# ESP32-HWE-Dev-Power.net
KiCad netlist of a schematic drawn in Altium Designer
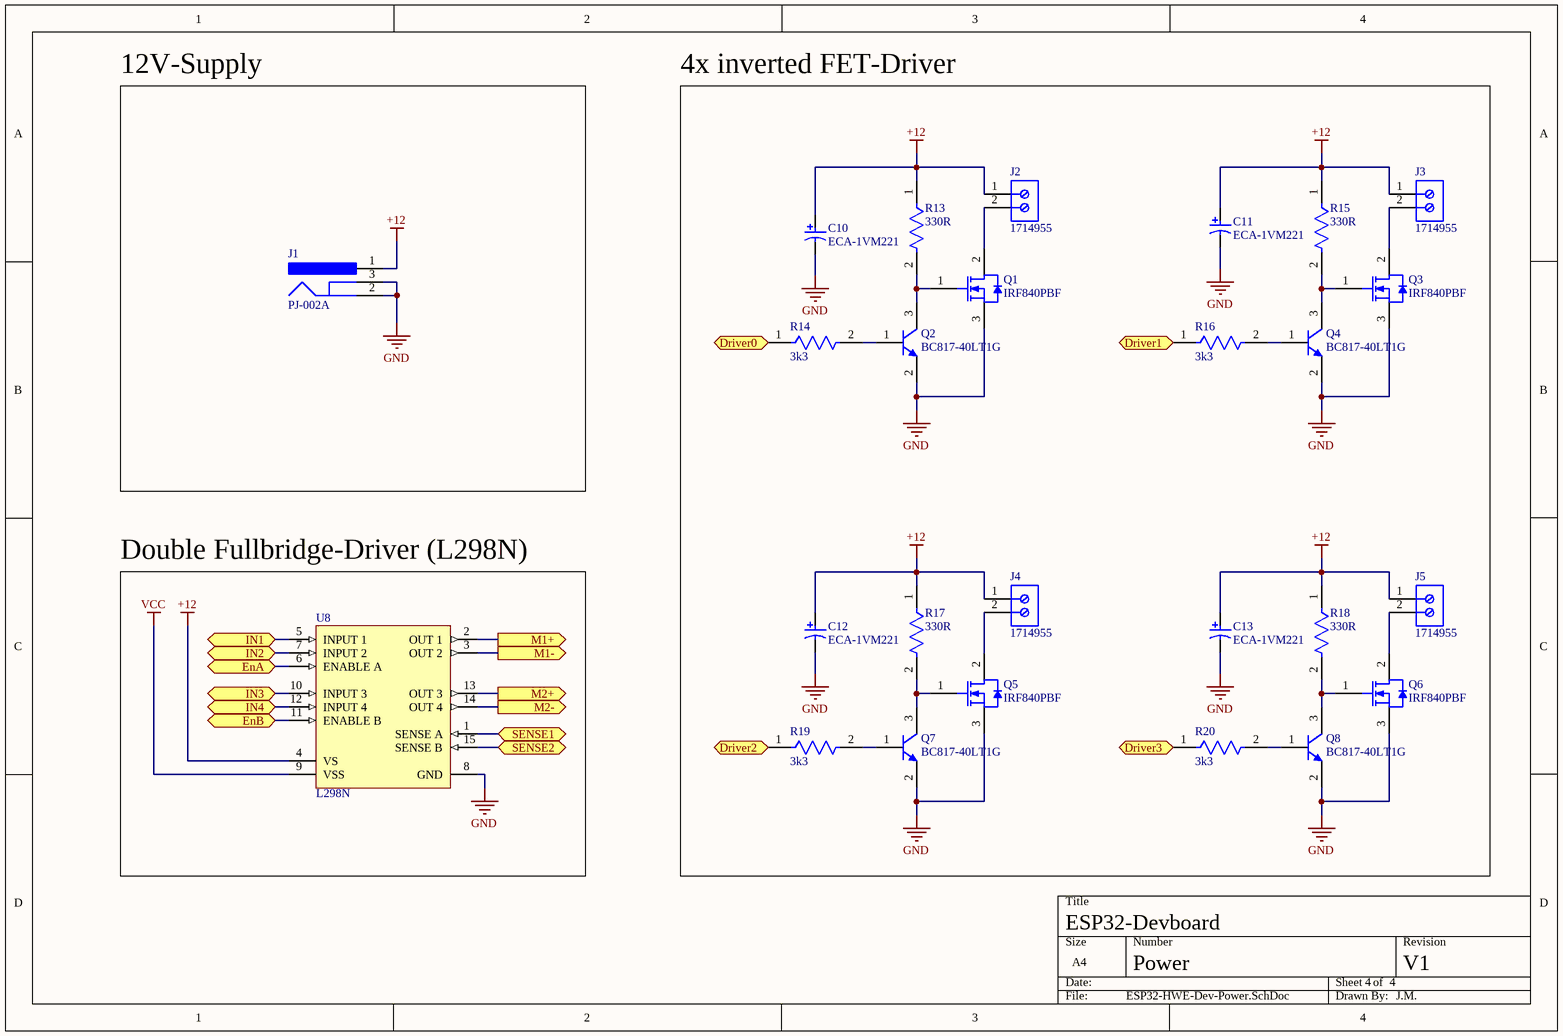
[diagram p0: ESP32-HWE-Dev-Power.SchDoc]

(export (version "E")
  (design (tool "Eeschema 10.0.6"))
  (components
    (comp (ref "C10")
      (value "ECA-1VM221")
      (footprint "PNSC-ECA-1VM221-2")
      (description "Aluminum Electrolytic Capacitor, 220 uF, +/- 20%, 35 V, -40 to 85 degC, 2-Pin THD, RoHS, Bulk")
      (fields (field (name "MANUFACTURER") "Panasonic"))
      (libsource (lib "Altium Content Vault") (part "CAP-P-2"))
    )
    (comp (ref "C11")
      (value "ECA-1VM221")
      (footprint "PNSC-ECA-1VM221-2")
      (description "Aluminum Electrolytic Capacitor, 220 uF, +/- 20%, 35 V, -40 to 85 degC, 2-Pin THD, RoHS, Bulk")
      (fields (field (name "MANUFACTURER") "Panasonic"))
      (libsource (lib "Altium Content Vault") (part "CAP-P-2"))
    )
    (comp (ref "C12")
      (value "ECA-1VM221")
      (footprint "PNSC-ECA-1VM221-2")
      (description "Aluminum Electrolytic Capacitor, 220 uF, +/- 20%, 35 V, -40 to 85 degC, 2-Pin THD, RoHS, Bulk")
      (fields (field (name "MANUFACTURER") "Panasonic"))
      (libsource (lib "Altium Content Vault") (part "CAP-P-2"))
    )
    (comp (ref "C13")
      (value "ECA-1VM221")
      (footprint "PNSC-ECA-1VM221-2")
      (description "Aluminum Electrolytic Capacitor, 220 uF, +/- 20%, 35 V, -40 to 85 degC, 2-Pin THD, RoHS, Bulk")
      (fields (field (name "MANUFACTURER") "Panasonic"))
      (libsource (lib "Altium Content Vault") (part "CAP-P-2"))
    )
    (comp (ref "J1")
      (value "PJ-002A")
      (footprint "CUI-PJ-002A_V")
      (fields (field (name "MANUFACTURER") "CUIInc."))
      (libsource (lib "Altium Content Vault") (part "JACK-2CD3-RN_B"))
    )
    (comp (ref "J2")
      (value "1714955")
      (footprint "PHOE-1714955_V")
      (description "PC Terminal Block, Pitch 6.35 mm, 1 x 2 Position, Height 21.5 mm, Tail Lenght 5.1 mm, RoHS, Bulk")
      (fields (field (name "MANUFACTURER") "Phoenix Contact"))
      (libsource (lib "Altium Content Vault") (part "CN-1P-F-TB2"))
    )
    (comp (ref "J3")
      (value "1714955")
      (footprint "PHOE-1714955_V")
      (description "PC Terminal Block, Pitch 6.35 mm, 1 x 2 Position, Height 21.5 mm, Tail Lenght 5.1 mm, RoHS, Bulk")
      (fields (field (name "MANUFACTURER") "Phoenix Contact"))
      (libsource (lib "Altium Content Vault") (part "CN-1P-F-TB2"))
    )
    (comp (ref "J4")
      (value "1714955")
      (footprint "PHOE-1714955_V")
      (description "PC Terminal Block, Pitch 6.35 mm, 1 x 2 Position, Height 21.5 mm, Tail Lenght 5.1 mm, RoHS, Bulk")
      (fields (field (name "MANUFACTURER") "Phoenix Contact"))
      (libsource (lib "Altium Content Vault") (part "CN-1P-F-TB2"))
    )
    (comp (ref "J5")
      (value "1714955")
      (footprint "PHOE-1714955_V")
      (description "PC Terminal Block, Pitch 6.35 mm, 1 x 2 Position, Height 21.5 mm, Tail Lenght 5.1 mm, RoHS, Bulk")
      (fields (field (name "MANUFACTURER") "Phoenix Contact"))
      (libsource (lib "Altium Content Vault") (part "CN-1P-F-TB2"))
    )
    (comp (ref "Q1")
      (value "IRF840PBF")
      (footprint "VISH-TO-220AB-3")
      (description "Power MOSFET, 500 V, -55 to 150 degC, 3-Pin FM, RoHS, Tape and Reel")
      (fields (field (name "MANUFACTURER") "Vishay"))
      (libsource (lib "Altium Content Vault") (part "NXP-NMOS-GDS-3"))
    )
    (comp (ref "Q2")
      (value "BC817-40LT1G")
      (footprint "ONSC-SOT-23-3-318-08_V")
      (description "General Purpose Transistor, NPN Silicon, 3-Pin SOT-23, Pb-Free, Tape and Reel")
      (fields (field (name "MANUFACTURER") "On Semiconductor"))
      (libsource (lib "Altium Content Vault") (part "ONSC-NPN-B1E2C3-3"))
    )
    (comp (ref "Q3")
      (value "IRF840PBF")
      (footprint "VISH-TO-220AB-3")
      (description "Power MOSFET, 500 V, -55 to 150 degC, 3-Pin FM, RoHS, Tape and Reel")
      (fields (field (name "MANUFACTURER") "Vishay"))
      (libsource (lib "Altium Content Vault") (part "NXP-NMOS-GDS-3"))
    )
    (comp (ref "Q4")
      (value "BC817-40LT1G")
      (footprint "ONSC-SOT-23-3-318-08_V")
      (description "General Purpose Transistor, NPN Silicon, 3-Pin SOT-23, Pb-Free, Tape and Reel")
      (fields (field (name "MANUFACTURER") "On Semiconductor"))
      (libsource (lib "Altium Content Vault") (part "ONSC-NPN-B1E2C3-3"))
    )
    (comp (ref "Q5")
      (value "IRF840PBF")
      (footprint "VISH-TO-220AB-3")
      (description "Power MOSFET, 500 V, -55 to 150 degC, 3-Pin FM, RoHS, Tape and Reel")
      (fields (field (name "MANUFACTURER") "Vishay"))
      (libsource (lib "Altium Content Vault") (part "NXP-NMOS-GDS-3"))
    )
    (comp (ref "Q6")
      (value "IRF840PBF")
      (footprint "VISH-TO-220AB-3")
      (description "Power MOSFET, 500 V, -55 to 150 degC, 3-Pin FM, RoHS, Tape and Reel")
      (fields (field (name "MANUFACTURER") "Vishay"))
      (libsource (lib "Altium Content Vault") (part "NXP-NMOS-GDS-3"))
    )
    (comp (ref "Q7")
      (value "BC817-40LT1G")
      (footprint "ONSC-SOT-23-3-318-08_V")
      (description "General Purpose Transistor, NPN Silicon, 3-Pin SOT-23, Pb-Free, Tape and Reel")
      (fields (field (name "MANUFACTURER") "On Semiconductor"))
      (libsource (lib "Altium Content Vault") (part "ONSC-NPN-B1E2C3-3"))
    )
    (comp (ref "Q8")
      (value "BC817-40LT1G")
      (footprint "ONSC-SOT-23-3-318-08_V")
      (description "General Purpose Transistor, NPN Silicon, 3-Pin SOT-23, Pb-Free, Tape and Reel")
      (fields (field (name "MANUFACTURER") "On Semiconductor"))
      (libsource (lib "Altium Content Vault") (part "ONSC-NPN-B1E2C3-3"))
    )
    (comp (ref "R13")
      (value "330R")
      (footprint "FP-AC0805-MFG")
      (description "RES SMD 4.7K OHM 5% 1/8W 0805")
      (fields (field (name "MANUFACTURER") "Yageo") (field (name "TOLERANCE") "0.05"))
      (libsource (lib "Altium Content Vault") (part "1029c3af85768c4190bb7ad29bc67b5"))
    )
    (comp (ref "R14")
      (value "3k3")
      (footprint "FP-AC0805-MFG")
      (description "RES SMD 4.7K OHM 5% 1/8W 0805")
      (fields (field (name "MANUFACTURER") "Yageo") (field (name "TOLERANCE") "0.05"))
      (libsource (lib "Altium Content Vault") (part "1029c3af85768c4190bb7ad29bc67b5"))
    )
    (comp (ref "R15")
      (value "330R")
      (footprint "FP-AC0805-MFG")
      (description "RES SMD 4.7K OHM 5% 1/8W 0805")
      (fields (field (name "MANUFACTURER") "Yageo") (field (name "TOLERANCE") "0.05"))
      (libsource (lib "Altium Content Vault") (part "1029c3af85768c4190bb7ad29bc67b5"))
    )
    (comp (ref "R16")
      (value "3k3")
      (footprint "FP-AC0805-MFG")
      (description "RES SMD 4.7K OHM 5% 1/8W 0805")
      (fields (field (name "MANUFACTURER") "Yageo") (field (name "TOLERANCE") "0.05"))
      (libsource (lib "Altium Content Vault") (part "1029c3af85768c4190bb7ad29bc67b5"))
    )
    (comp (ref "R17")
      (value "330R")
      (footprint "FP-AC0805-MFG")
      (description "RES SMD 4.7K OHM 5% 1/8W 0805")
      (fields (field (name "MANUFACTURER") "Yageo") (field (name "TOLERANCE") "0.05"))
      (libsource (lib "Altium Content Vault") (part "1029c3af85768c4190bb7ad29bc67b5"))
    )
    (comp (ref "R18")
      (value "330R")
      (footprint "FP-AC0805-MFG")
      (description "RES SMD 4.7K OHM 5% 1/8W 0805")
      (fields (field (name "MANUFACTURER") "Yageo") (field (name "TOLERANCE") "0.05"))
      (libsource (lib "Altium Content Vault") (part "1029c3af85768c4190bb7ad29bc67b5"))
    )
    (comp (ref "R19")
      (value "3k3")
      (footprint "FP-AC0805-MFG")
      (description "RES SMD 4.7K OHM 5% 1/8W 0805")
      (fields (field (name "MANUFACTURER") "Yageo") (field (name "TOLERANCE") "0.05"))
      (libsource (lib "Altium Content Vault") (part "1029c3af85768c4190bb7ad29bc67b5"))
    )
    (comp (ref "R20")
      (value "3k3")
      (footprint "FP-AC0805-MFG")
      (description "RES SMD 4.7K OHM 5% 1/8W 0805")
      (fields (field (name "MANUFACTURER") "Yageo") (field (name "TOLERANCE") "0.05"))
      (libsource (lib "Altium Content Vault") (part "1029c3af85768c4190bb7ad29bc67b5"))
    )
    (comp (ref "U8")
      (value "L298N")
      (footprint "STM-FM-15")
      (description "Dual Full-Bridge Driver, 4.8 to 46 V, -40 to 150 degC, 15-Pin FM (MW 15L), RoHS, Tube")
      (fields (field (name "MANUFACTURER") "STMicroelectronics") (field (name "PARTNUMBER") "L298"))
      (libsource (lib "Altium Content Vault") (part "STM-L298-15"))
    )
  )
  (nets
    (net (code "1") (name "+12") (class "Default")
      (node (ref "C10") (pin "1") (pinfunction "1_1") (pintype "passive"))
      (node (ref "C11") (pin "1") (pinfunction "1_1") (pintype "passive"))
      (node (ref "C12") (pin "1") (pinfunction "1_1") (pintype "passive"))
      (node (ref "C13") (pin "1") (pinfunction "1_1") (pintype "passive"))
      (node (ref "J1") (pin "1") (pinfunction "1_1") (pintype "passive"))
      (node (ref "J2") (pin "1") (pinfunction "1_1") (pintype "passive"))
      (node (ref "J3") (pin "1") (pinfunction "1_1") (pintype "passive"))
      (node (ref "J4") (pin "1") (pinfunction "1_1") (pintype "passive"))
      (node (ref "J5") (pin "1") (pinfunction "1_1") (pintype "passive"))
      (node (ref "R13") (pin "1") (pinfunction "1_1") (pintype "passive"))
      (node (ref "R15") (pin "1") (pinfunction "1_1") (pintype "passive"))
      (node (ref "R17") (pin "1") (pinfunction "1_1") (pintype "passive"))
      (node (ref "R18") (pin "1") (pinfunction "1_1") (pintype "passive"))
      (node (ref "U8") (pin "4") (pinfunction "VS_4") (pintype "power_in"))
    )
    (net (code "2") (name "/Driver0") (class "Default")
      (node (ref "R14") (pin "1") (pinfunction "1_1") (pintype "passive"))
    )
    (net (code "3") (name "/Driver1") (class "Default")
      (node (ref "R16") (pin "1") (pinfunction "1_1") (pintype "passive"))
    )
    (net (code "4") (name "/Driver2") (class "Default")
      (node (ref "R19") (pin "1") (pinfunction "1_1") (pintype "passive"))
    )
    (net (code "5") (name "/Driver3") (class "Default")
      (node (ref "R20") (pin "1") (pinfunction "1_1") (pintype "passive"))
    )
    (net (code "6") (name "/EnA") (class "Default")
      (node (ref "U8") (pin "6") (pinfunction "ENABLE_A_6") (pintype "input"))
    )
    (net (code "7") (name "/EnB") (class "Default")
      (node (ref "U8") (pin "11") (pinfunction "ENABLE_B_11") (pintype "input"))
    )
    (net (code "8") (name "/IN1") (class "Default")
      (node (ref "U8") (pin "5") (pinfunction "INPUT_1_5") (pintype "input"))
    )
    (net (code "9") (name "/IN2") (class "Default")
      (node (ref "U8") (pin "7") (pinfunction "INPUT_2_7") (pintype "input"))
    )
    (net (code "10") (name "/IN3") (class "Default")
      (node (ref "U8") (pin "10") (pinfunction "INPUT_3_10") (pintype "input"))
    )
    (net (code "11") (name "/IN4") (class "Default")
      (node (ref "U8") (pin "12") (pinfunction "INPUT_4_12") (pintype "input"))
    )
    (net (code "12") (name "/M1+") (class "Default")
      (node (ref "U8") (pin "2") (pinfunction "OUT_1_2") (pintype "output"))
    )
    (net (code "13") (name "/M1-") (class "Default")
      (node (ref "U8") (pin "3") (pinfunction "OUT_2_3") (pintype "output"))
    )
    (net (code "14") (name "/M2+") (class "Default")
      (node (ref "U8") (pin "13") (pinfunction "OUT_3_13") (pintype "output"))
    )
    (net (code "15") (name "/M2-") (class "Default")
      (node (ref "U8") (pin "14") (pinfunction "OUT_4_14") (pintype "output"))
    )
    (net (code "16") (name "/SENSE1") (class "Default")
      (node (ref "U8") (pin "1") (pinfunction "SENSE_A_1") (pintype "input"))
    )
    (net (code "17") (name "/SENSE2") (class "Default")
      (node (ref "U8") (pin "15") (pinfunction "SENSE_B_15") (pintype "input"))
    )
    (net (code "18") (name "GND") (class "Default")
      (node (ref "C10") (pin "2") (pinfunction "2_2") (pintype "passive"))
      (node (ref "C11") (pin "2") (pinfunction "2_2") (pintype "passive"))
      (node (ref "C12") (pin "2") (pinfunction "2_2") (pintype "passive"))
      (node (ref "C13") (pin "2") (pinfunction "2_2") (pintype "passive"))
      (node (ref "J1") (pin "2") (pinfunction "2_2") (pintype "passive"))
      (node (ref "J1") (pin "3") (pinfunction "3_3") (pintype "passive"))
      (node (ref "Q1") (pin "3") (pinfunction "S_3") (pintype "passive"))
      (node (ref "Q2") (pin "2") (pinfunction "E_2") (pintype "passive"))
      (node (ref "Q3") (pin "3") (pinfunction "S_3") (pintype "passive"))
      (node (ref "Q4") (pin "2") (pinfunction "E_2") (pintype "passive"))
      (node (ref "Q5") (pin "3") (pinfunction "S_3") (pintype "passive"))
      (node (ref "Q6") (pin "3") (pinfunction "S_3") (pintype "passive"))
      (node (ref "Q7") (pin "2") (pinfunction "E_2") (pintype "passive"))
      (node (ref "Q8") (pin "2") (pinfunction "E_2") (pintype "passive"))
      (node (ref "U8") (pin "8") (pinfunction "GND_8") (pintype "power_in"))
    )
    (net (code "19") (name "Net-(Q1-D)") (class "Default")
      (node (ref "J2") (pin "2") (pinfunction "2_2") (pintype "passive"))
      (node (ref "Q1") (pin "2") (pinfunction "D_2") (pintype "passive"))
    )
    (net (code "20") (name "Net-(Q1-G)") (class "Default")
      (node (ref "Q1") (pin "1") (pinfunction "G_1") (pintype "passive"))
      (node (ref "Q2") (pin "3") (pinfunction "C_3") (pintype "passive"))
      (node (ref "R13") (pin "2") (pinfunction "2_2") (pintype "passive"))
    )
    (net (code "21") (name "Net-(Q2-B)") (class "Default")
      (node (ref "Q2") (pin "1") (pinfunction "B_1") (pintype "passive"))
      (node (ref "R14") (pin "2") (pinfunction "2_2") (pintype "passive"))
    )
    (net (code "22") (name "Net-(Q3-D)") (class "Default")
      (node (ref "J3") (pin "2") (pinfunction "2_2") (pintype "passive"))
      (node (ref "Q3") (pin "2") (pinfunction "D_2") (pintype "passive"))
    )
    (net (code "23") (name "Net-(Q3-G)") (class "Default")
      (node (ref "Q3") (pin "1") (pinfunction "G_1") (pintype "passive"))
      (node (ref "Q4") (pin "3") (pinfunction "C_3") (pintype "passive"))
      (node (ref "R15") (pin "2") (pinfunction "2_2") (pintype "passive"))
    )
    (net (code "24") (name "Net-(Q4-B)") (class "Default")
      (node (ref "Q4") (pin "1") (pinfunction "B_1") (pintype "passive"))
      (node (ref "R16") (pin "2") (pinfunction "2_2") (pintype "passive"))
    )
    (net (code "25") (name "Net-(Q5-D)") (class "Default")
      (node (ref "J4") (pin "2") (pinfunction "2_2") (pintype "passive"))
      (node (ref "Q5") (pin "2") (pinfunction "D_2") (pintype "passive"))
    )
    (net (code "26") (name "Net-(Q5-G)") (class "Default")
      (node (ref "Q5") (pin "1") (pinfunction "G_1") (pintype "passive"))
      (node (ref "Q7") (pin "3") (pinfunction "C_3") (pintype "passive"))
      (node (ref "R17") (pin "2") (pinfunction "2_2") (pintype "passive"))
    )
    (net (code "27") (name "Net-(Q6-D)") (class "Default")
      (node (ref "J5") (pin "2") (pinfunction "2_2") (pintype "passive"))
      (node (ref "Q6") (pin "2") (pinfunction "D_2") (pintype "passive"))
    )
    (net (code "28") (name "Net-(Q6-G)") (class "Default")
      (node (ref "Q6") (pin "1") (pinfunction "G_1") (pintype "passive"))
      (node (ref "Q8") (pin "3") (pinfunction "C_3") (pintype "passive"))
      (node (ref "R18") (pin "2") (pinfunction "2_2") (pintype "passive"))
    )
    (net (code "29") (name "Net-(Q7-B)") (class "Default")
      (node (ref "Q7") (pin "1") (pinfunction "B_1") (pintype "passive"))
      (node (ref "R19") (pin "2") (pinfunction "2_2") (pintype "passive"))
    )
    (net (code "30") (name "Net-(Q8-B)") (class "Default")
      (node (ref "Q8") (pin "1") (pinfunction "B_1") (pintype "passive"))
      (node (ref "R20") (pin "2") (pinfunction "2_2") (pintype "passive"))
    )
    (net (code "31") (name "VCC") (class "Default")
      (node (ref "U8") (pin "9") (pinfunction "VSS_9") (pintype "power_in"))
    )
  )
)
